# servopoinB3.net
KiCad netlist of a schematic drawn in EAGLE
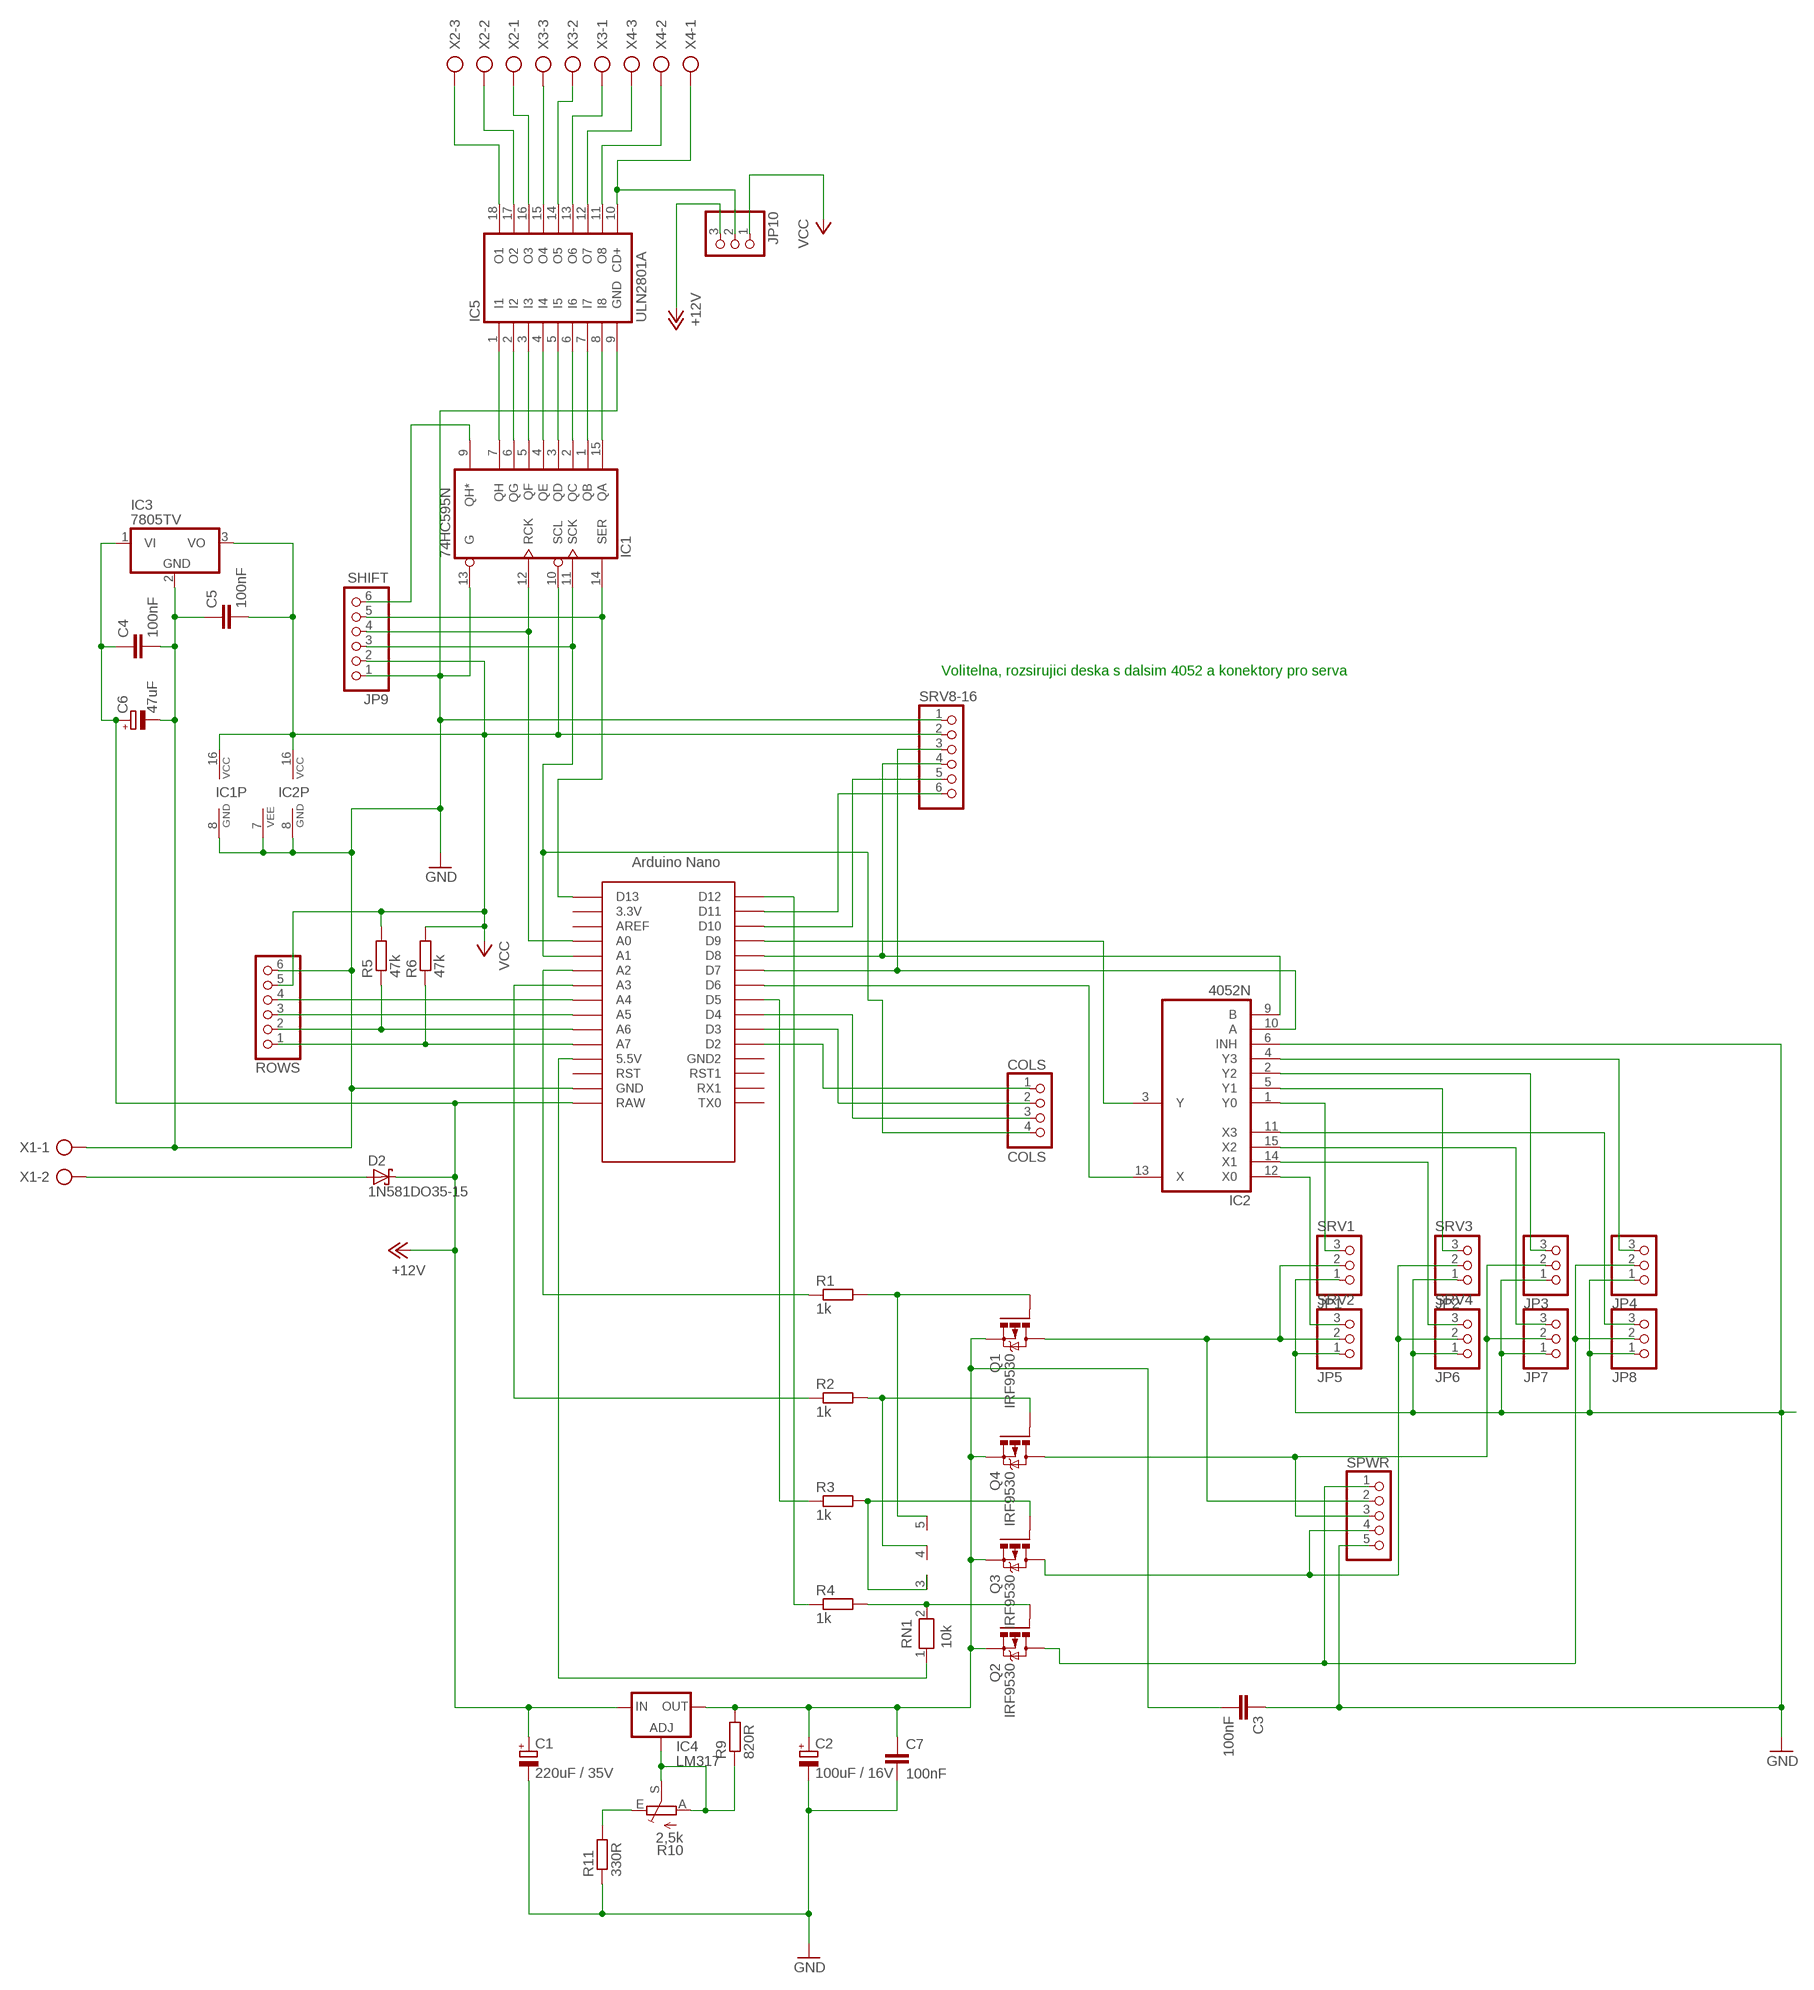
[diagram p0: schematic, sheet 1]

(export (version "E")
  (design (tool "Eeschema 10.0.6"))
  (components
    (comp (ref "C1")
      (value "220uF / 35V")
      (footprint "eagle-import:E5-10,5")
      (libsource (lib "eagle-import") (part "resistor_CPOL-EUE5-10.5"))
    )
    (comp (ref "C2")
      (value "100uF / 16V")
      (footprint "eagle-import:E2,5-5")
      (libsource (lib "eagle-import") (part "resistor_CPOL-EUE2.5-5"))
    )
    (comp (ref "C3")
      (value "100nF")
      (footprint "eagle-import:C025-025X050")
      (libsource (lib "eagle-import") (part "resistor_C-EU025-025X050"))
    )
    (comp (ref "C4")
      (value "100nF")
      (footprint "eagle-import:C025-025X050")
      (libsource (lib "eagle-import") (part "C-EU025-025X050"))
    )
    (comp (ref "C5")
      (value "100nF")
      (footprint "eagle-import:C025-025X050")
      (libsource (lib "eagle-import") (part "C-EU025-025X050"))
    )
    (comp (ref "C6")
      (value "47uF")
      (footprint "eagle-import:E2,5-6")
      (libsource (lib "eagle-import") (part "CPOL-EUE2.5-6"))
    )
    (comp (ref "C7")
      (value "100nF")
      (footprint "eagle-import:C025-025X050")
      (libsource (lib "eagle-import") (part "resistor_C-EU025-025X050"))
    )
    (comp (ref "COLS")
      (value "COLS")
      (footprint "eagle-import:1X04")
      (libsource (lib "eagle-import") (part "PINHD-1X4"))
    )
    (comp (ref "D2")
      (value "1N581DO35-15")
      (footprint "eagle-import:DO35-10")
      (libsource (lib "eagle-import") (part "1N581DO35-15"))
    )
    (comp (ref "IC1")
      (value "74HC595N")
      (footprint "eagle-import:DIL16")
      (libsource (lib "eagle-import") (part "74595NHC"))
    )
    (comp (ref "IC2")
      (value "4052N")
      (footprint "eagle-import:DIL16")
      (libsource (lib "eagle-import") (part "4052N"))
    )
    (comp (ref "IC3")
      (value "7805TV")
      (footprint "eagle-import:TO220V")
      (libsource (lib "eagle-import") (part "78TV05"))
    )
    (comp (ref "IC4")
      (value "LM317")
      (footprint "eagle-import:317TS")
      (libsource (lib "eagle-import") (part "LM317TS"))
    )
    (comp (ref "IC5")
      (value "ULN2801A")
      (footprint "eagle-import:DIL18")
      (libsource (lib "eagle-import") (part "ULN2801A"))
    )
    (comp (ref "JP1")
      (value "SRV1")
      (footprint "eagle-import:1X03")
      (libsource (lib "eagle-import") (part "PINHD-1X3"))
    )
    (comp (ref "JP2")
      (value "SRV3")
      (footprint "eagle-import:1X03")
      (libsource (lib "eagle-import") (part "PINHD-1X3"))
    )
    (comp (ref "JP3")
      (value "PINHD-1X3")
      (footprint "eagle-import:1X03")
      (libsource (lib "eagle-import") (part "PINHD-1X3"))
    )
    (comp (ref "JP4")
      (value "PINHD-1X3")
      (footprint "eagle-import:1X03")
      (libsource (lib "eagle-import") (part "PINHD-1X3"))
    )
    (comp (ref "JP5")
      (value "SRV2")
      (footprint "eagle-import:1X03")
      (libsource (lib "eagle-import") (part "PINHD-1X3"))
    )
    (comp (ref "JP6")
      (value "SRV4")
      (footprint "eagle-import:1X03")
      (libsource (lib "eagle-import") (part "PINHD-1X3"))
    )
    (comp (ref "JP7")
      (value "PINHD-1X3")
      (footprint "eagle-import:1X03")
      (libsource (lib "eagle-import") (part "PINHD-1X3"))
    )
    (comp (ref "JP8")
      (value "PINHD-1X3")
      (footprint "eagle-import:1X03")
      (libsource (lib "eagle-import") (part "PINHD-1X3"))
    )
    (comp (ref "JP9")
      (value "SHIFT")
      (footprint "eagle-import:1X06")
      (libsource (lib "eagle-import") (part "PINHD-1X6"))
    )
    (comp (ref "JP10")
      (value "PINHD-1X3")
      (footprint "eagle-import:1X03")
      (libsource (lib "eagle-import") (part "PINHD-1X3"))
    )
    (comp (ref "Q1")
      (value "IRF9530")
      (footprint "eagle-import:TO220BV")
      (libsource (lib "eagle-import") (part "IRF9530"))
    )
    (comp (ref "Q2")
      (value "IRF9530")
      (footprint "eagle-import:TO220BV")
      (libsource (lib "eagle-import") (part "IRF9530"))
    )
    (comp (ref "Q3")
      (value "IRF9530")
      (footprint "eagle-import:TO220BV")
      (libsource (lib "eagle-import") (part "IRF9530"))
    )
    (comp (ref "Q4")
      (value "IRF9530")
      (footprint "eagle-import:TO220BV")
      (libsource (lib "eagle-import") (part "IRF9530"))
    )
    (comp (ref "R1")
      (value "1k")
      (footprint "eagle-import:0207_10")
      (libsource (lib "eagle-import") (part "R-EU_0207/10"))
    )
    (comp (ref "R2")
      (value "1k")
      (footprint "eagle-import:0207_10")
      (libsource (lib "eagle-import") (part "R-EU_0207/10"))
    )
    (comp (ref "R3")
      (value "1k")
      (footprint "eagle-import:0207_10")
      (libsource (lib "eagle-import") (part "R-EU_0207/10"))
    )
    (comp (ref "R4")
      (value "1k")
      (footprint "eagle-import:0207_10")
      (libsource (lib "eagle-import") (part "R-EU_0207/10"))
    )
    (comp (ref "R5")
      (value "47k")
      (footprint "eagle-import:0207_10")
      (libsource (lib "eagle-import") (part "R-EU_0207/10"))
    )
    (comp (ref "R6")
      (value "47k")
      (footprint "eagle-import:0207_10")
      (libsource (lib "eagle-import") (part "R-EU_0207/10"))
    )
    (comp (ref "R9")
      (value "820R")
      (footprint "eagle-import:0207_10")
      (libsource (lib "eagle-import") (part "R-EU_0207/10"))
    )
    (comp (ref "R10")
      (value "2,5k")
      (footprint "eagle-import:LI10")
      (libsource (lib "eagle-import") (part "TRIM_EU-LI10-PADS"))
    )
    (comp (ref "R11")
      (value "330R")
      (footprint "eagle-import:0207_10")
      (libsource (lib "eagle-import") (part "R-EU_0207/10"))
    )
    (comp (ref "RN1")
      (value "10k")
      (footprint "eagle-import:RN-5")
      (libsource (lib "eagle-import") (part "RN04"))
    )
    (comp (ref "ROWS")
      (value "PINHD-1X6")
      (footprint "eagle-import:1X06")
      (libsource (lib "eagle-import") (part "PINHD-1X6"))
    )
    (comp (ref "SPWR")
      (value "PINHD-1X5")
      (footprint "eagle-import:1X05")
      (libsource (lib "eagle-import") (part "PINHD-1X5"))
    )
    (comp (ref "SRV8-16")
      (value "PINHD-1X6")
      (footprint "eagle-import:1X06")
      (libsource (lib "eagle-import") (part "PINHD-1X6"))
    )
    (comp (ref "U$1")
      (value "NANO")
      (footprint "eagle-import:NANO")
      (libsource (lib "eagle-import") (part "NANO"))
    )
    (comp (ref "X1")
      (value "AK500/2")
      (footprint "eagle-import:AK500_2")
      (libsource (lib "eagle-import") (part "AK500/2"))
    )
    (comp (ref "X2")
      (value "AK500/3")
      (footprint "eagle-import:AK500_3")
      (libsource (lib "eagle-import") (part "AK500/3"))
    )
    (comp (ref "X3")
      (value "AK500/3")
      (footprint "eagle-import:AK500_3")
      (libsource (lib "eagle-import") (part "AK500/3"))
    )
    (comp (ref "X4")
      (value "AK500/3")
      (footprint "eagle-import:AK500_3")
      (libsource (lib "eagle-import") (part "AK500/3"))
    )
  )
  (nets
    (net (code "1") (name "+12V") (class "Default")
      (node (ref "C1") (pin "+") (pinfunction "+_+") (pintype "passive"))
      (node (ref "C4") (pin "1") (pinfunction "1_1") (pintype "passive"))
      (node (ref "C6") (pin "+") (pinfunction "+_+") (pintype "passive"))
      (node (ref "D2") (pin "C") (pinfunction "C_C") (pintype "passive"))
      (node (ref "IC3") (pin "1") (pinfunction "VI_1") (pintype "input"))
      (node (ref "IC4") (pin "3") (pinfunction "IN_3") (pintype "input"))
      (node (ref "JP10") (pin "3") (pinfunction "3_3") (pintype "passive"))
      (node (ref "U$1") (pin "RAW") (pinfunction "RAW_RAW") (pintype "bidirectional"))
    )
    (net (code "2") (name "GND") (class "Default")
      (node (ref "C1") (pin "-") (pinfunction "-_-") (pintype "passive"))
      (node (ref "C2") (pin "-") (pinfunction "-_-") (pintype "passive"))
      (node (ref "C3") (pin "1") (pinfunction "1_1") (pintype "passive"))
      (node (ref "C4") (pin "2") (pinfunction "2_2") (pintype "passive"))
      (node (ref "C5") (pin "1") (pinfunction "1_1") (pintype "passive"))
      (node (ref "C6") (pin "-") (pinfunction "-_-") (pintype "passive"))
      (node (ref "C7") (pin "2") (pinfunction "2_2") (pintype "passive"))
      (node (ref "IC1") (pin "13") (pinfunction "G_13") (pintype "input"))
      (node (ref "IC1") (pin "8") (pinfunction "GND_8") (pintype "power_in"))
      (node (ref "IC2") (pin "6") (pinfunction "INH_6") (pintype "input"))
      (node (ref "IC2") (pin "7") (pinfunction "VEE_7") (pintype "power_in"))
      (node (ref "IC2") (pin "8") (pinfunction "GND_8") (pintype "power_in"))
      (node (ref "IC3") (pin "2") (pinfunction "GND_2") (pintype "passive"))
      (node (ref "IC5") (pin "9") (pinfunction "GND_9") (pintype "power_in"))
      (node (ref "JP1") (pin "1") (pinfunction "1_1") (pintype "passive"))
      (node (ref "JP2") (pin "1") (pinfunction "1_1") (pintype "passive"))
      (node (ref "JP3") (pin "1") (pinfunction "1_1") (pintype "passive"))
      (node (ref "JP4") (pin "1") (pinfunction "1_1") (pintype "passive"))
      (node (ref "JP5") (pin "1") (pinfunction "1_1") (pintype "passive"))
      (node (ref "JP6") (pin "1") (pinfunction "1_1") (pintype "passive"))
      (node (ref "JP7") (pin "1") (pinfunction "1_1") (pintype "passive"))
      (node (ref "JP8") (pin "1") (pinfunction "1_1") (pintype "passive"))
      (node (ref "JP9") (pin "1") (pinfunction "1_1") (pintype "passive"))
      (node (ref "R11") (pin "1") (pinfunction "1_1") (pintype "passive"))
      (node (ref "ROWS") (pin "6") (pinfunction "6_6") (pintype "passive"))
      (node (ref "SPWR") (pin "5") (pinfunction "5_5") (pintype "passive"))
      (node (ref "SRV8-16") (pin "1") (pinfunction "1_1") (pintype "passive"))
      (node (ref "U$1") (pin "GND") (pinfunction "GND_GND") (pintype "bidirectional"))
      (node (ref "X1") (pin "1") (pinfunction "KL_1") (pintype "passive"))
    )
    (net (code "3") (name "Net-(COLS-Pad1)") (class "Default")
      (node (ref "COLS") (pin "1") (pinfunction "1_1") (pintype "passive"))
      (node (ref "U$1") (pin "D2") (pinfunction "D2_D2") (pintype "bidirectional"))
    )
    (net (code "4") (name "Net-(COLS-Pad2)") (class "Default")
      (node (ref "COLS") (pin "2") (pinfunction "2_2") (pintype "passive"))
      (node (ref "U$1") (pin "D3") (pinfunction "D3_D3") (pintype "bidirectional"))
    )
    (net (code "5") (name "Net-(COLS-Pad3)") (class "Default")
      (node (ref "COLS") (pin "3") (pinfunction "3_3") (pintype "passive"))
      (node (ref "U$1") (pin "D4") (pinfunction "D4_D4") (pintype "bidirectional"))
    )
    (net (code "6") (name "Net-(IC1A-QA)") (class "Default")
      (node (ref "IC1") (pin "15") (pinfunction "QA_15") (pintype "tri_state"))
      (node (ref "IC5") (pin "8") (pinfunction "I8_8") (pintype "input"))
    )
    (net (code "7") (name "Net-(IC1A-QB)") (class "Default")
      (node (ref "IC1") (pin "1") (pinfunction "QB_1") (pintype "tri_state"))
      (node (ref "IC5") (pin "7") (pinfunction "I7_7") (pintype "input"))
    )
    (net (code "8") (name "Net-(IC1A-QC)") (class "Default")
      (node (ref "IC1") (pin "2") (pinfunction "QC_2") (pintype "tri_state"))
      (node (ref "IC5") (pin "6") (pinfunction "I6_6") (pintype "input"))
    )
    (net (code "9") (name "Net-(IC1A-QD)") (class "Default")
      (node (ref "IC1") (pin "3") (pinfunction "QD_3") (pintype "tri_state"))
      (node (ref "IC5") (pin "5") (pinfunction "I5_5") (pintype "input"))
    )
    (net (code "10") (name "Net-(IC1A-QE)") (class "Default")
      (node (ref "IC1") (pin "4") (pinfunction "QE_4") (pintype "tri_state"))
      (node (ref "IC5") (pin "4") (pinfunction "I4_4") (pintype "input"))
    )
    (net (code "11") (name "Net-(IC1A-QF)") (class "Default")
      (node (ref "IC1") (pin "5") (pinfunction "QF_5") (pintype "tri_state"))
      (node (ref "IC5") (pin "3") (pinfunction "I3_3") (pintype "input"))
    )
    (net (code "12") (name "Net-(IC1A-QG)") (class "Default")
      (node (ref "IC1") (pin "6") (pinfunction "QG_6") (pintype "tri_state"))
      (node (ref "IC5") (pin "2") (pinfunction "I2_2") (pintype "input"))
    )
    (net (code "13") (name "Net-(IC1A-QH)") (class "Default")
      (node (ref "IC1") (pin "7") (pinfunction "QH_7") (pintype "tri_state"))
      (node (ref "IC5") (pin "1") (pinfunction "I1_1") (pintype "input"))
    )
    (net (code "14") (name "Net-(IC1A-QH*)") (class "Default")
      (node (ref "IC1") (pin "9") (pinfunction "QH*_9") (pintype "tri_state"))
      (node (ref "JP9") (pin "6") (pinfunction "6_6") (pintype "passive"))
    )
    (net (code "15") (name "Net-(IC1A-RCK)") (class "Default")
      (node (ref "IC1") (pin "12") (pinfunction "RCK_12") (pintype "input"))
      (node (ref "JP9") (pin "4") (pinfunction "4_4") (pintype "passive"))
      (node (ref "U$1") (pin "A0") (pinfunction "A0_A0") (pintype "bidirectional"))
    )
    (net (code "16") (name "Net-(IC1A-SCK)") (class "Default")
      (node (ref "COLS") (pin "4") (pinfunction "4_4") (pintype "passive"))
      (node (ref "IC1") (pin "11") (pinfunction "SCK_11") (pintype "input"))
      (node (ref "JP9") (pin "3") (pinfunction "3_3") (pintype "passive"))
      (node (ref "U$1") (pin "A1") (pinfunction "A1_A1") (pintype "bidirectional"))
    )
    (net (code "17") (name "Net-(IC1A-SER)") (class "Default")
      (node (ref "IC1") (pin "14") (pinfunction "SER_14") (pintype "input"))
      (node (ref "JP9") (pin "5") (pinfunction "5_5") (pintype "passive"))
      (node (ref "U$1") (pin "D13") (pinfunction "D13_D13") (pintype "bidirectional"))
    )
    (net (code "18") (name "Net-(IC2A-A)") (class "Default")
      (node (ref "IC2") (pin "10") (pinfunction "A_10") (pintype "input"))
      (node (ref "SRV8-16") (pin "3") (pinfunction "3_3") (pintype "passive"))
      (node (ref "U$1") (pin "D7") (pinfunction "D7_D7") (pintype "bidirectional"))
    )
    (net (code "19") (name "Net-(IC2A-B)") (class "Default")
      (node (ref "IC2") (pin "9") (pinfunction "B_9") (pintype "input"))
      (node (ref "SRV8-16") (pin "4") (pinfunction "4_4") (pintype "passive"))
      (node (ref "U$1") (pin "D8") (pinfunction "D8_D8") (pintype "bidirectional"))
    )
    (net (code "20") (name "Net-(IC2A-X)") (class "Default")
      (node (ref "IC2") (pin "13") (pinfunction "X_13") (pintype "bidirectional"))
      (node (ref "U$1") (pin "D6") (pinfunction "D6_D6") (pintype "bidirectional"))
    )
    (net (code "21") (name "Net-(IC2A-X0)") (class "Default")
      (node (ref "IC2") (pin "12") (pinfunction "X0_12") (pintype "bidirectional"))
      (node (ref "JP5") (pin "3") (pinfunction "3_3") (pintype "passive"))
    )
    (net (code "22") (name "Net-(IC2A-X1)") (class "Default")
      (node (ref "IC2") (pin "14") (pinfunction "X1_14") (pintype "bidirectional"))
      (node (ref "JP6") (pin "3") (pinfunction "3_3") (pintype "passive"))
    )
    (net (code "23") (name "Net-(IC2A-X2)") (class "Default")
      (node (ref "IC2") (pin "15") (pinfunction "X2_15") (pintype "bidirectional"))
      (node (ref "JP7") (pin "3") (pinfunction "3_3") (pintype "passive"))
    )
    (net (code "24") (name "Net-(IC2A-X3)") (class "Default")
      (node (ref "IC2") (pin "11") (pinfunction "X3_11") (pintype "bidirectional"))
      (node (ref "JP8") (pin "3") (pinfunction "3_3") (pintype "passive"))
    )
    (net (code "25") (name "Net-(IC2A-Y)") (class "Default")
      (node (ref "IC2") (pin "3") (pinfunction "Y_3") (pintype "bidirectional"))
      (node (ref "U$1") (pin "D9") (pinfunction "D9_D9") (pintype "bidirectional"))
    )
    (net (code "26") (name "Net-(IC2A-Y0)") (class "Default")
      (node (ref "IC2") (pin "1") (pinfunction "Y0_1") (pintype "bidirectional"))
      (node (ref "JP1") (pin "3") (pinfunction "3_3") (pintype "passive"))
    )
    (net (code "27") (name "Net-(IC2A-Y1)") (class "Default")
      (node (ref "IC2") (pin "5") (pinfunction "Y1_5") (pintype "bidirectional"))
      (node (ref "JP2") (pin "3") (pinfunction "3_3") (pintype "passive"))
    )
    (net (code "28") (name "Net-(IC2A-Y2)") (class "Default")
      (node (ref "IC2") (pin "2") (pinfunction "Y2_2") (pintype "bidirectional"))
      (node (ref "JP3") (pin "3") (pinfunction "3_3") (pintype "passive"))
    )
    (net (code "29") (name "Net-(IC2A-Y3)") (class "Default")
      (node (ref "IC2") (pin "4") (pinfunction "Y3_4") (pintype "bidirectional"))
      (node (ref "JP4") (pin "3") (pinfunction "3_3") (pintype "passive"))
    )
    (net (code "30") (name "Net-(IC4-ADJ)") (class "Default")
      (node (ref "IC4") (pin "1") (pinfunction "ADJ_1") (pintype "input"))
      (node (ref "R10") (pin "A") (pinfunction "A_A") (pintype "passive"))
      (node (ref "R10") (pin "S") (pinfunction "S_S") (pintype "passive"))
      (node (ref "R9") (pin "1") (pinfunction "1_1") (pintype "passive"))
    )
    (net (code "31") (name "Net-(IC4-OUT)") (class "Default")
      (node (ref "C2") (pin "+") (pinfunction "+_+") (pintype "passive"))
      (node (ref "C3") (pin "2") (pinfunction "2_2") (pintype "passive"))
      (node (ref "C7") (pin "1") (pinfunction "1_1") (pintype "passive"))
      (node (ref "IC4") (pin "2") (pinfunction "OUT_2") (pintype "passive"))
      (node (ref "Q1") (pin "S") (pinfunction "S_S") (pintype "passive"))
      (node (ref "Q2") (pin "S") (pinfunction "S_S") (pintype "passive"))
      (node (ref "Q3") (pin "S") (pinfunction "S_S") (pintype "passive"))
      (node (ref "Q4") (pin "S") (pinfunction "S_S") (pintype "passive"))
      (node (ref "R9") (pin "2") (pinfunction "2_2") (pintype "passive"))
    )
    (net (code "32") (name "Net-(IC5-CD+)") (class "Default")
      (node (ref "IC5") (pin "10") (pinfunction "CD+_10") (pintype "passive"))
      (node (ref "JP10") (pin "2") (pinfunction "2_2") (pintype "passive"))
      (node (ref "X4") (pin "1") (pinfunction "KL_1") (pintype "passive"))
    )
    (net (code "33") (name "Net-(IC5-O1)") (class "Default")
      (node (ref "IC5") (pin "18") (pinfunction "O1_18") (pintype "open_collector"))
      (node (ref "X2") (pin "3") (pinfunction "KL_3") (pintype "passive"))
    )
    (net (code "34") (name "Net-(IC5-O2)") (class "Default")
      (node (ref "IC5") (pin "17") (pinfunction "O2_17") (pintype "open_collector"))
      (node (ref "X2") (pin "2") (pinfunction "KL_2") (pintype "passive"))
    )
    (net (code "35") (name "Net-(IC5-O3)") (class "Default")
      (node (ref "IC5") (pin "16") (pinfunction "O3_16") (pintype "open_collector"))
      (node (ref "X2") (pin "1") (pinfunction "KL_1") (pintype "passive"))
    )
    (net (code "36") (name "Net-(IC5-O4)") (class "Default")
      (node (ref "IC5") (pin "15") (pinfunction "O4_15") (pintype "open_collector"))
      (node (ref "X3") (pin "3") (pinfunction "KL_3") (pintype "passive"))
    )
    (net (code "37") (name "Net-(IC5-O5)") (class "Default")
      (node (ref "IC5") (pin "14") (pinfunction "O5_14") (pintype "open_collector"))
      (node (ref "X3") (pin "2") (pinfunction "KL_2") (pintype "passive"))
    )
    (net (code "38") (name "Net-(IC5-O6)") (class "Default")
      (node (ref "IC5") (pin "13") (pinfunction "O6_13") (pintype "open_collector"))
      (node (ref "X3") (pin "1") (pinfunction "KL_1") (pintype "passive"))
    )
    (net (code "39") (name "Net-(IC5-O7)") (class "Default")
      (node (ref "IC5") (pin "12") (pinfunction "O7_12") (pintype "open_collector"))
      (node (ref "X4") (pin "3") (pinfunction "KL_3") (pintype "passive"))
    )
    (net (code "40") (name "Net-(IC5-O8)") (class "Default")
      (node (ref "IC5") (pin "11") (pinfunction "O8_11") (pintype "open_collector"))
      (node (ref "X4") (pin "2") (pinfunction "KL_2") (pintype "passive"))
    )
    (net (code "41") (name "Net-(JP1-Pad2)") (class "Default")
      (node (ref "JP1") (pin "2") (pinfunction "2_2") (pintype "passive"))
      (node (ref "JP5") (pin "2") (pinfunction "2_2") (pintype "passive"))
      (node (ref "Q1") (pin "D") (pinfunction "D_D") (pintype "passive"))
      (node (ref "SPWR") (pin "2") (pinfunction "2_2") (pintype "passive"))
    )
    (net (code "42") (name "Net-(JP2-Pad2)") (class "Default")
      (node (ref "JP2") (pin "2") (pinfunction "2_2") (pintype "passive"))
      (node (ref "JP6") (pin "2") (pinfunction "2_2") (pintype "passive"))
      (node (ref "Q3") (pin "D") (pinfunction "D_D") (pintype "passive"))
      (node (ref "SPWR") (pin "4") (pinfunction "4_4") (pintype "passive"))
    )
    (net (code "43") (name "Net-(JP3-Pad2)") (class "Default")
      (node (ref "JP3") (pin "2") (pinfunction "2_2") (pintype "passive"))
      (node (ref "JP7") (pin "2") (pinfunction "2_2") (pintype "passive"))
      (node (ref "Q4") (pin "D") (pinfunction "D_D") (pintype "passive"))
      (node (ref "SPWR") (pin "3") (pinfunction "3_3") (pintype "passive"))
    )
    (net (code "44") (name "Net-(JP4-Pad2)") (class "Default")
      (node (ref "JP4") (pin "2") (pinfunction "2_2") (pintype "passive"))
      (node (ref "JP8") (pin "2") (pinfunction "2_2") (pintype "passive"))
      (node (ref "Q2") (pin "D") (pinfunction "D_D") (pintype "passive"))
      (node (ref "SPWR") (pin "1") (pinfunction "1_1") (pintype "passive"))
    )
    (net (code "45") (name "Net-(Q1-PadG)") (class "Default")
      (node (ref "Q1") (pin "G") (pinfunction "G_G") (pintype "passive"))
      (node (ref "R1") (pin "2") (pinfunction "2_2") (pintype "passive"))
      (node (ref "RN1") (pin "5") (pinfunction "5_5") (pintype "passive"))
    )
    (net (code "46") (name "Net-(Q2-PadG)") (class "Default")
      (node (ref "Q2") (pin "G") (pinfunction "G_G") (pintype "passive"))
      (node (ref "R4") (pin "2") (pinfunction "2_2") (pintype "passive"))
      (node (ref "RN1") (pin "2") (pinfunction "2_2") (pintype "passive"))
    )
    (net (code "47") (name "Net-(Q3-PadG)") (class "Default")
      (node (ref "Q3") (pin "G") (pinfunction "G_G") (pintype "passive"))
      (node (ref "R3") (pin "2") (pinfunction "2_2") (pintype "passive"))
      (node (ref "RN1") (pin "3") (pinfunction "3_3") (pintype "passive"))
    )
    (net (code "48") (name "Net-(Q4-PadG)") (class "Default")
      (node (ref "Q4") (pin "G") (pinfunction "G_G") (pintype "passive"))
      (node (ref "R2") (pin "2") (pinfunction "2_2") (pintype "passive"))
      (node (ref "RN1") (pin "4") (pinfunction "4_4") (pintype "passive"))
    )
    (net (code "49") (name "Net-(R1-Pad1)") (class "Default")
      (node (ref "R1") (pin "1") (pinfunction "1_1") (pintype "passive"))
      (node (ref "U$1") (pin "A2") (pinfunction "A2_A2") (pintype "bidirectional"))
    )
    (net (code "50") (name "Net-(R2-Pad1)") (class "Default")
      (node (ref "R2") (pin "1") (pinfunction "1_1") (pintype "passive"))
      (node (ref "U$1") (pin "A3") (pinfunction "A3_A3") (pintype "bidirectional"))
    )
    (net (code "51") (name "Net-(R3-Pad1)") (class "Default")
      (node (ref "R3") (pin "1") (pinfunction "1_1") (pintype "passive"))
      (node (ref "U$1") (pin "D5") (pinfunction "D5_D5") (pintype "bidirectional"))
    )
    (net (code "52") (name "Net-(R4-Pad1)") (class "Default")
      (node (ref "R4") (pin "1") (pinfunction "1_1") (pintype "passive"))
      (node (ref "U$1") (pin "D12") (pinfunction "D12_D12") (pintype "bidirectional"))
    )
    (net (code "53") (name "Net-(R5-Pad1)") (class "Default")
      (node (ref "R5") (pin "1") (pinfunction "1_1") (pintype "passive"))
      (node (ref "ROWS") (pin "2") (pinfunction "2_2") (pintype "passive"))
      (node (ref "U$1") (pin "A6") (pinfunction "A6_A6") (pintype "bidirectional"))
    )
    (net (code "54") (name "Net-(R6-Pad1)") (class "Default")
      (node (ref "R6") (pin "1") (pinfunction "1_1") (pintype "passive"))
      (node (ref "ROWS") (pin "1") (pinfunction "1_1") (pintype "passive"))
      (node (ref "U$1") (pin "A7") (pinfunction "A7_A7") (pintype "bidirectional"))
    )
    (net (code "55") (name "Net-(R10-PadE)") (class "Default")
      (node (ref "R10") (pin "E") (pinfunction "E_E") (pintype "passive"))
      (node (ref "R11") (pin "2") (pinfunction "2_2") (pintype "passive"))
    )
    (net (code "56") (name "Net-(ROWS-Pad3)") (class "Default")
      (node (ref "ROWS") (pin "3") (pinfunction "3_3") (pintype "passive"))
      (node (ref "U$1") (pin "A5") (pinfunction "A5_A5") (pintype "bidirectional"))
    )
    (net (code "57") (name "Net-(ROWS-Pad4)") (class "Default")
      (node (ref "ROWS") (pin "4") (pinfunction "4_4") (pintype "passive"))
      (node (ref "U$1") (pin "A4") (pinfunction "A4_A4") (pintype "bidirectional"))
    )
    (net (code "58") (name "Net-(SRV8-16-Pad5)") (class "Default")
      (node (ref "SRV8-16") (pin "5") (pinfunction "5_5") (pintype "passive"))
      (node (ref "U$1") (pin "D10") (pinfunction "D10_D10") (pintype "bidirectional"))
    )
    (net (code "59") (name "Net-(SRV8-16-Pad6)") (class "Default")
      (node (ref "SRV8-16") (pin "6") (pinfunction "6_6") (pintype "passive"))
      (node (ref "U$1") (pin "D11") (pinfunction "D11_D11") (pintype "bidirectional"))
    )
    (net (code "60") (name "Net-(U$1-5.5V)") (class "Default")
      (node (ref "RN1") (pin "1") (pinfunction "1_1") (pintype "passive"))
      (node (ref "U$1") (pin "5V") (pinfunction "5.5V_5V") (pintype "bidirectional"))
    )
    (net (code "61") (name "Net-(X1B-KL)") (class "Default")
      (node (ref "D2") (pin "A") (pinfunction "A_A") (pintype "passive"))
      (node (ref "X1") (pin "2") (pinfunction "KL_2") (pintype "passive"))
    )
    (net (code "62") (name "VCC") (class "Default")
      (node (ref "C5") (pin "2") (pinfunction "2_2") (pintype "passive"))
      (node (ref "IC1") (pin "10") (pinfunction "SCL_10") (pintype "input"))
      (node (ref "IC1") (pin "16") (pinfunction "VCC_16") (pintype "power_in"))
      (node (ref "IC2") (pin "16") (pinfunction "VCC_16") (pintype "power_in"))
      (node (ref "IC3") (pin "3") (pinfunction "VO_3") (pintype "passive"))
      (node (ref "JP10") (pin "1") (pinfunction "1_1") (pintype "passive"))
      (node (ref "JP9") (pin "2") (pinfunction "2_2") (pintype "passive"))
      (node (ref "R5") (pin "2") (pinfunction "2_2") (pintype "passive"))
      (node (ref "R6") (pin "2") (pinfunction "2_2") (pintype "passive"))
      (node (ref "ROWS") (pin "5") (pinfunction "5_5") (pintype "passive"))
      (node (ref "SRV8-16") (pin "2") (pinfunction "2_2") (pintype "passive"))
    )
    (net (code "63") (name "unconnected-(U$1-GND2-PadGND1)") (class "Default")
      (node (ref "U$1") (pin "GND1") (pinfunction "GND2_GND1") (pintype "bidirectional"))
    )
    (net (code "64") (name "unconnected-(U$1-Pad3.3V)") (class "Default")
      (node (ref "U$1") (pin "3.3V") (pinfunction "3.3V_3.3V") (pintype "bidirectional"))
    )
    (net (code "65") (name "unconnected-(U$1-PadAREF)") (class "Default")
      (node (ref "U$1") (pin "AREF") (pinfunction "AREF_AREF") (pintype "bidirectional"))
    )
    (net (code "66") (name "unconnected-(U$1-PadICSP1)") (class "Default")
      (node (ref "U$1") (pin "ICSP1") (pinfunction "ICSP1_ICSP1") (pintype "bidirectional"))
    )
    (net (code "67") (name "unconnected-(U$1-PadICSP2)") (class "Default")
      (node (ref "U$1") (pin "ICSP2") (pinfunction "ICSP2_ICSP2") (pintype "bidirectional"))
    )
    (net (code "68") (name "unconnected-(U$1-PadICSP3)") (class "Default")
      (node (ref "U$1") (pin "ICSP3") (pinfunction "ICSP3_ICSP3") (pintype "bidirectional"))
    )
    (net (code "69") (name "unconnected-(U$1-PadICSP4)") (class "Default")
      (node (ref "U$1") (pin "ICSP4") (pinfunction "ICSP4_ICSP4") (pintype "bidirectional"))
    )
    (net (code "70") (name "unconnected-(U$1-PadICSP5)") (class "Default")
      (node (ref "U$1") (pin "ICSP5") (pinfunction "ICSP5_ICSP5") (pintype "bidirectional"))
    )
    (net (code "71") (name "unconnected-(U$1-PadICSP6)") (class "Default")
      (node (ref "U$1") (pin "ICSP6") (pinfunction "ICSP6_ICSP6") (pintype "bidirectional"))
    )
    (net (code "72") (name "unconnected-(U$1-PadRST)") (class "Default")
      (node (ref "U$1") (pin "RST") (pinfunction "RST_RST") (pintype "bidirectional"))
    )
    (net (code "73") (name "unconnected-(U$1-PadRST1)") (class "Default")
      (node (ref "U$1") (pin "RST1") (pinfunction "RST1_RST1") (pintype "bidirectional"))
    )
    (net (code "74") (name "unconnected-(U$1-PadRX1)") (class "Default")
      (node (ref "U$1") (pin "RX1") (pinfunction "RX1_RX1") (pintype "bidirectional"))
    )
    (net (code "75") (name "unconnected-(U$1-PadTX0)") (class "Default")
      (node (ref "U$1") (pin "TX0") (pinfunction "TX0_TX0") (pintype "bidirectional"))
    )
  )
)
